# OutputPowerModule.net
KiCad netlist of a schematic drawn in Altium Designer
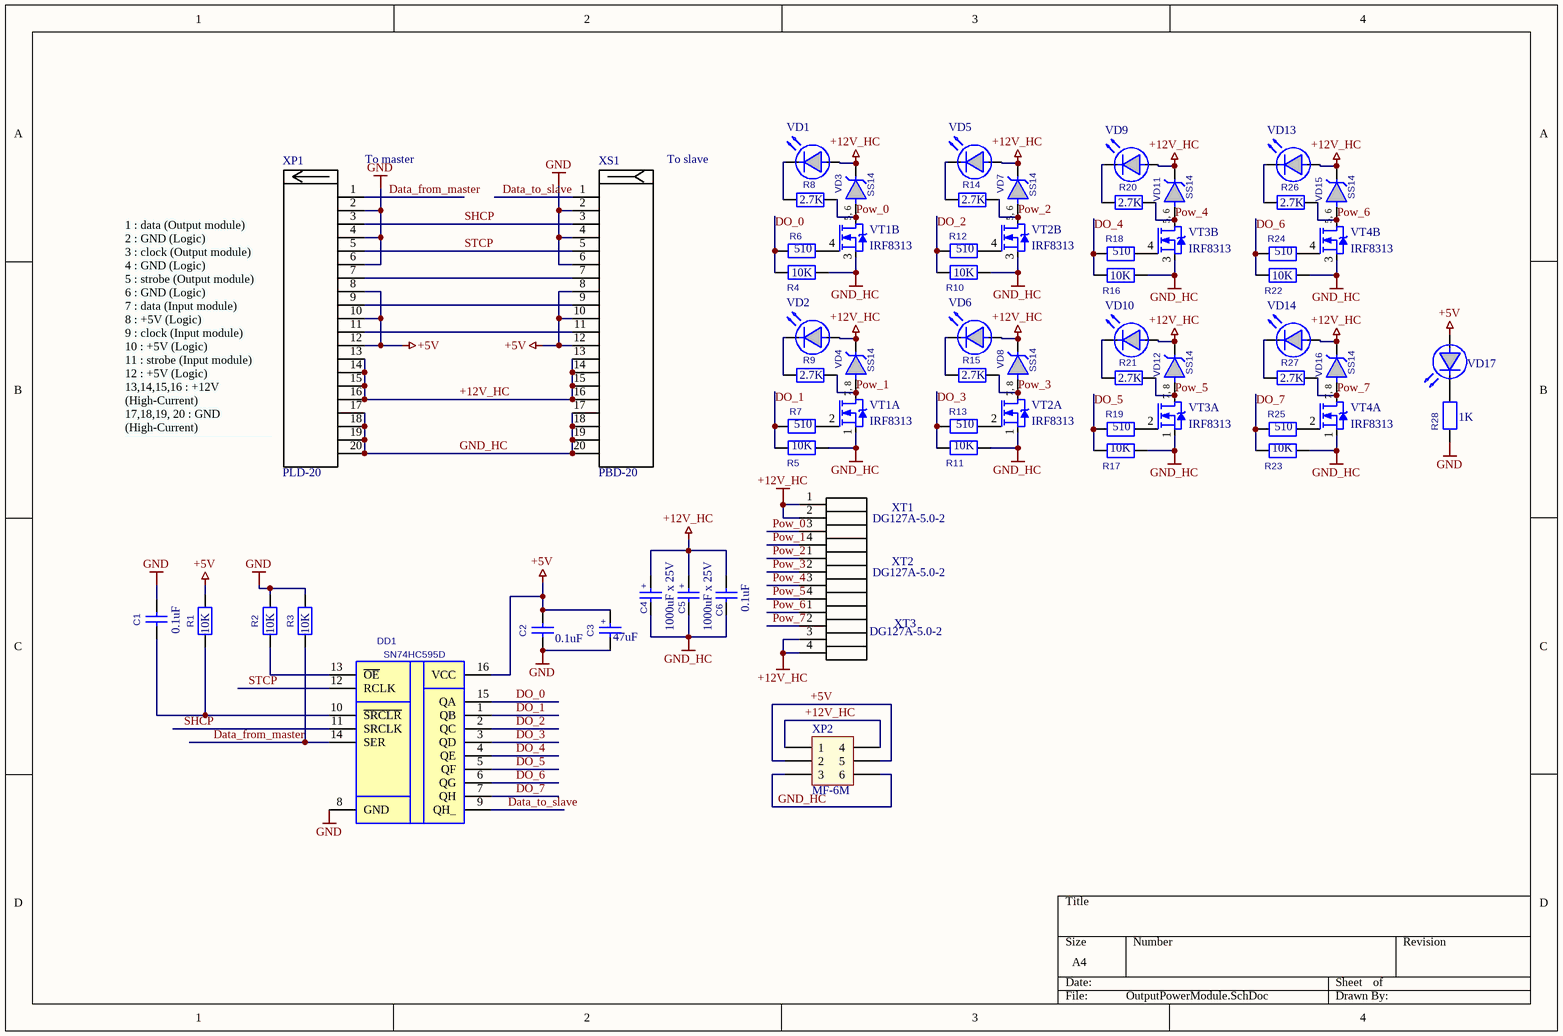
[diagram p0: OutputPowerModule.SchDoc]

(export (version "E")
  (design (tool "Eeschema 10.0.6"))
  (components
    (comp (ref "C1")
      (value "0.1uF")
      (footprint "C-1608[0603]")
      (description "C-0603")
      (libsource (lib "Altium-RC") (part "C-0603"))
    )
    (comp (ref "C2")
      (value "0.1uF")
      (footprint "C-1608[0603]")
      (description "C-0603")
      (libsource (lib "Altium-RC") (part "C-0603"))
    )
    (comp (ref "C3")
      (value "47uF")
      (footprint "C-CASE")
      (description "C-CCASE")
      (libsource (lib "Altium-RC") (part "C-CCASE"))
    )
    (comp (ref "C4")
      (value "1000uF x 25V")
      (footprint "D10-5MM")
      (description "K50-35(D10MM)")
      (libsource (lib "Altium-RC") (part "K50-35(D10MM)"))
    )
    (comp (ref "C5")
      (value "1000uF x 25V")
      (footprint "D10-5MM")
      (description "K50-35(D10MM)")
      (libsource (lib "Altium-RC") (part "K50-35(D10MM)"))
    )
    (comp (ref "C6")
      (value "0.1uF")
      (footprint "C-1608[0603]")
      (description "C-0603")
      (libsource (lib "Altium-RC") (part "C-0603"))
    )
    (comp (ref "DD1")
      (value "SN74HC595D")
      (footprint "SO-G16")
      (libsource (lib "Altium-IC") (part "SN74HC595D"))
    )
    (comp (ref "R1")
      (value "10K")
      (footprint "R-1608[0603]")
      (description "R-0603")
      (libsource (lib "Altium-RC") (part "R-0603"))
    )
    (comp (ref "R2")
      (value "10K")
      (footprint "R-1608[0603]")
      (description "R-0603")
      (libsource (lib "Altium-RC") (part "R-0603"))
    )
    (comp (ref "R3")
      (value "10K")
      (footprint "R-1608[0603]")
      (description "R-0603")
      (libsource (lib "Altium-RC") (part "R-0603"))
    )
    (comp (ref "R4")
      (value "10K")
      (footprint "R-1608[0603]")
      (description "R-0603")
      (libsource (lib "Altium-RC") (part "R-0603"))
    )
    (comp (ref "R5")
      (value "10K")
      (footprint "R-1608[0603]")
      (description "R-0603")
      (libsource (lib "Altium-RC") (part "R-0603"))
    )
    (comp (ref "R6")
      (value "510")
      (footprint "R-1608[0603]")
      (description "R-0603")
      (libsource (lib "Altium-RC") (part "R-0603"))
    )
    (comp (ref "R7")
      (value "510")
      (footprint "R-1608[0603]")
      (description "R-0603")
      (libsource (lib "Altium-RC") (part "R-0603"))
    )
    (comp (ref "R8")
      (value "2.7K")
      (footprint "R-1608[0603]")
      (description "R-0603")
      (libsource (lib "Altium-RC") (part "R-0603"))
    )
    (comp (ref "R9")
      (value "2.7K")
      (footprint "R-1608[0603]")
      (description "R-0603")
      (libsource (lib "Altium-RC") (part "R-0603"))
    )
    (comp (ref "R10")
      (value "10K")
      (footprint "R-1608[0603]")
      (description "R-0603")
      (libsource (lib "Altium-RC") (part "R-0603"))
    )
    (comp (ref "R11")
      (value "10K")
      (footprint "R-1608[0603]")
      (description "R-0603")
      (libsource (lib "Altium-RC") (part "R-0603"))
    )
    (comp (ref "R12")
      (value "510")
      (footprint "R-1608[0603]")
      (description "R-0603")
      (libsource (lib "Altium-RC") (part "R-0603"))
    )
    (comp (ref "R13")
      (value "510")
      (footprint "R-1608[0603]")
      (description "R-0603")
      (libsource (lib "Altium-RC") (part "R-0603"))
    )
    (comp (ref "R14")
      (value "2.7K")
      (footprint "R-1608[0603]")
      (description "R-0603")
      (libsource (lib "Altium-RC") (part "R-0603"))
    )
    (comp (ref "R15")
      (value "2.7K")
      (footprint "R-1608[0603]")
      (description "R-0603")
      (libsource (lib "Altium-RC") (part "R-0603"))
    )
    (comp (ref "R16")
      (value "10K")
      (footprint "R-1608[0603]")
      (description "R-0603")
      (libsource (lib "Altium-RC") (part "R-0603"))
    )
    (comp (ref "R17")
      (value "10K")
      (footprint "R-1608[0603]")
      (description "R-0603")
      (libsource (lib "Altium-RC") (part "R-0603"))
    )
    (comp (ref "R18")
      (value "510")
      (footprint "R-1608[0603]")
      (description "R-0603")
      (libsource (lib "Altium-RC") (part "R-0603"))
    )
    (comp (ref "R19")
      (value "510")
      (footprint "R-1608[0603]")
      (description "R-0603")
      (libsource (lib "Altium-RC") (part "R-0603"))
    )
    (comp (ref "R20")
      (value "2.7K")
      (footprint "R-1608[0603]")
      (description "R-0603")
      (libsource (lib "Altium-RC") (part "R-0603"))
    )
    (comp (ref "R21")
      (value "2.7K")
      (footprint "R-1608[0603]")
      (description "R-0603")
      (libsource (lib "Altium-RC") (part "R-0603"))
    )
    (comp (ref "R22")
      (value "10K")
      (footprint "R-1608[0603]")
      (description "R-0603")
      (libsource (lib "Altium-RC") (part "R-0603"))
    )
    (comp (ref "R23")
      (value "10K")
      (footprint "R-1608[0603]")
      (description "R-0603")
      (libsource (lib "Altium-RC") (part "R-0603"))
    )
    (comp (ref "R24")
      (value "510")
      (footprint "R-1608[0603]")
      (description "R-0603")
      (libsource (lib "Altium-RC") (part "R-0603"))
    )
    (comp (ref "R25")
      (value "510")
      (footprint "R-1608[0603]")
      (description "R-0603")
      (libsource (lib "Altium-RC") (part "R-0603"))
    )
    (comp (ref "R26")
      (value "2.7K")
      (footprint "R-1608[0603]")
      (description "R-0603")
      (libsource (lib "Altium-RC") (part "R-0603"))
    )
    (comp (ref "R27")
      (value "2.7K")
      (footprint "R-1608[0603]")
      (description "R-0603")
      (libsource (lib "Altium-RC") (part "R-0603"))
    )
    (comp (ref "R28")
      (value "1K")
      (footprint "R-1608[0603]")
      (description "R-0603")
      (libsource (lib "Altium-RC") (part "R-0603"))
    )
    (comp (ref "VD1")
      (value "L-C191KGCT")
      (footprint "LED-0603")
      (description "0603 Green Led")
      (libsource (lib "Altium-OPTO") (part "L-C191KGCT"))
    )
    (comp (ref "VD2")
      (value "L-C191KGCT")
      (footprint "LED-0603")
      (description "0603 Green Led")
      (libsource (lib "Altium-OPTO") (part "L-C191KGCT"))
    )
    (comp (ref "VD3") (value "SS14") (footprint "SMA") (libsource (lib "Altium-RECT") (part "SS16")))
    (comp (ref "VD4") (value "SS14") (footprint "SMA") (libsource (lib "Altium-RECT") (part "SS16")))
    (comp (ref "VD5")
      (value "L-C191KGCT")
      (footprint "LED-0603")
      (description "0603 Green Led")
      (libsource (lib "Altium-OPTO") (part "L-C191KGCT"))
    )
    (comp (ref "VD6")
      (value "L-C191KGCT")
      (footprint "LED-0603")
      (description "0603 Green Led")
      (libsource (lib "Altium-OPTO") (part "L-C191KGCT"))
    )
    (comp (ref "VD7") (value "SS14") (footprint "SMA") (libsource (lib "Altium-RECT") (part "SS16")))
    (comp (ref "VD8") (value "SS14") (footprint "SMA") (libsource (lib "Altium-RECT") (part "SS16")))
    (comp (ref "VD9")
      (value "L-C191KGCT")
      (footprint "LED-0603")
      (description "0603 Green Led")
      (libsource (lib "Altium-OPTO") (part "L-C191KGCT"))
    )
    (comp (ref "VD10")
      (value "L-C191KGCT")
      (footprint "LED-0603")
      (description "0603 Green Led")
      (libsource (lib "Altium-OPTO") (part "L-C191KGCT"))
    )
    (comp (ref "VD11") (value "SS14") (footprint "SMA") (libsource (lib "Altium-RECT") (part "SS16")))
    (comp (ref "VD12") (value "SS14") (footprint "SMA") (libsource (lib "Altium-RECT") (part "SS16")))
    (comp (ref "VD13")
      (value "L-C191KGCT")
      (footprint "LED-0603")
      (description "0603 Green Led")
      (libsource (lib "Altium-OPTO") (part "L-C191KGCT"))
    )
    (comp (ref "VD14")
      (value "L-C191KGCT")
      (footprint "LED-0603")
      (description "0603 Green Led")
      (libsource (lib "Altium-OPTO") (part "L-C191KGCT"))
    )
    (comp (ref "VD15") (value "SS14") (footprint "SMA") (libsource (lib "Altium-RECT") (part "SS16")))
    (comp (ref "VD16") (value "SS14") (footprint "SMA") (libsource (lib "Altium-RECT") (part "SS16")))
    (comp (ref "VD17")
      (value "L-C191KGCT")
      (footprint "LED-0603")
      (description "0603 Green Led")
      (libsource (lib "") (part "L-C191KGCT_1"))
    )
    (comp (ref "VT1")
      (value "IRF8313")
      (footprint "SO8")
      (description "HEXFET Power MOSFET N channel")
      (libsource (lib "Altium-RECT") (part "IRF8313"))
    )
    (comp (ref "VT2")
      (value "IRF8313")
      (footprint "SO8")
      (description "HEXFET Power MOSFET N channel")
      (libsource (lib "Altium-RECT") (part "IRF8313"))
    )
    (comp (ref "VT3")
      (value "IRF8313")
      (footprint "SO8")
      (description "HEXFET Power MOSFET N channel")
      (libsource (lib "Altium-RECT") (part "IRF8313"))
    )
    (comp (ref "VT4")
      (value "IRF8313")
      (footprint "SO8")
      (description "HEXFET Power MOSFET N channel")
      (libsource (lib "Altium-RECT") (part "IRF8313"))
    )
    (comp (ref "XP1")
      (value "PLD-20")
      (footprint "PLD-20 ROT")
      (description "20 pin, 2 row, MALE connector")
      (libsource (lib "Altium-CONN") (part "PLD-20"))
    )
    (comp (ref "XP2")
      (value "MF-6M")
      (footprint "MF-6M")
      (description "Molex Male connector")
      (libsource (lib "Altium-CONN") (part "MF-6M"))
    )
    (comp (ref "XS1")
      (value "PBD-20")
      (footprint "PBD-20 Rot")
      (description "2.54mm, 20 pin FEMALE connector")
      (libsource (lib "Altium-CONN") (part "PBD-20"))
    )
    (comp (ref "XT1")
      (value "DG127A-5.0-2")
      (footprint "DG127A-5.0-2")
      (description "Клеммник винтовой двухр дный шаг 5.0 мм 2х2 контактов")
      (libsource (lib "Altium-CONN") (part "DG127A-5.0-2"))
    )
    (comp (ref "XT2")
      (value "DG127A-5.0-2")
      (footprint "DG127A-5.0-2")
      (description "Клеммник винтовой двухр дный шаг 5.0 мм 2х2 контактов")
      (libsource (lib "Altium-CONN") (part "DG127A-5.0-2"))
    )
    (comp (ref "XT3")
      (value "DG127A-5.0-2")
      (footprint "DG127A-5.0-2")
      (description "Клеммник винтовой двухр дный шаг 5.0 мм 2х2 контактов")
      (libsource (lib "Altium-CONN") (part "DG127A-5.0-2"))
    )
  )
  (nets
    (net (code "1") (name "+5V") (class "Default")
      (node (ref "C2") (pin "1") (pintype "passive"))
      (node (ref "C3") (pin "1") (pinfunction "+_1") (pintype "passive"))
      (node (ref "DD1") (pin "16") (pinfunction "VCC_16") (pintype "passive"))
      (node (ref "R1") (pin "2") (pinfunction "2_2") (pintype "passive"))
      (node (ref "VD17") (pin "2") (pinfunction "A_2") (pintype "passive"))
      (node (ref "XP1") (pin "10") (pintype "passive"))
      (node (ref "XP1") (pin "12") (pintype "passive"))
      (node (ref "XP1") (pin "8") (pintype "passive"))
      (node (ref "XP2") (pin "2") (pinfunction "2_2") (pintype "passive"))
      (node (ref "XP2") (pin "5") (pinfunction "5_5") (pintype "passive"))
      (node (ref "XS1") (pin "10") (pintype "passive"))
      (node (ref "XS1") (pin "12") (pintype "passive"))
      (node (ref "XS1") (pin "8") (pintype "passive"))
    )
    (net (code "2") (name "+12V_HC") (class "Default")
      (node (ref "C4") (pin "1") (pinfunction "+_1") (pintype "passive"))
      (node (ref "C5") (pin "1") (pinfunction "+_1") (pintype "passive"))
      (node (ref "C6") (pin "1") (pintype "passive"))
      (node (ref "VD1") (pin "2") (pinfunction "A_2") (pintype "passive"))
      (node (ref "VD10") (pin "2") (pinfunction "A_2") (pintype "passive"))
      (node (ref "VD11") (pin "1") (pinfunction "K_1") (pintype "passive"))
      (node (ref "VD12") (pin "1") (pinfunction "K_1") (pintype "passive"))
      (node (ref "VD13") (pin "2") (pinfunction "A_2") (pintype "passive"))
      (node (ref "VD14") (pin "2") (pinfunction "A_2") (pintype "passive"))
      (node (ref "VD15") (pin "1") (pinfunction "K_1") (pintype "passive"))
      (node (ref "VD16") (pin "1") (pinfunction "K_1") (pintype "passive"))
      (node (ref "VD2") (pin "2") (pinfunction "A_2") (pintype "passive"))
      (node (ref "VD3") (pin "1") (pinfunction "K_1") (pintype "passive"))
      (node (ref "VD4") (pin "1") (pinfunction "K_1") (pintype "passive"))
      (node (ref "VD5") (pin "2") (pinfunction "A_2") (pintype "passive"))
      (node (ref "VD6") (pin "2") (pinfunction "A_2") (pintype "passive"))
      (node (ref "VD7") (pin "1") (pinfunction "K_1") (pintype "passive"))
      (node (ref "VD8") (pin "1") (pinfunction "K_1") (pintype "passive"))
      (node (ref "VD9") (pin "2") (pinfunction "A_2") (pintype "passive"))
      (node (ref "XP1") (pin "13") (pintype "passive"))
      (node (ref "XP1") (pin "14") (pintype "passive"))
      (node (ref "XP1") (pin "15") (pintype "passive"))
      (node (ref "XP1") (pin "16") (pintype "passive"))
      (node (ref "XP2") (pin "1") (pinfunction "1_1") (pintype "passive"))
      (node (ref "XP2") (pin "4") (pinfunction "4_4") (pintype "passive"))
      (node (ref "XS1") (pin "13") (pintype "passive"))
      (node (ref "XS1") (pin "14") (pintype "passive"))
      (node (ref "XS1") (pin "15") (pintype "passive"))
      (node (ref "XS1") (pin "16") (pintype "passive"))
      (node (ref "XT1") (pin "1") (pinfunction "1_1") (pintype "passive"))
      (node (ref "XT1") (pin "2") (pinfunction "2_2") (pintype "passive"))
      (node (ref "XT3") (pin "3") (pinfunction "3_3") (pintype "passive"))
      (node (ref "XT3") (pin "4") (pinfunction "4_4") (pintype "passive"))
    )
    (net (code "3") (name "/DO_0") (class "Default")
      (node (ref "DD1") (pin "15") (pinfunction "QA_15") (pintype "passive"))
      (node (ref "R4") (pin "1") (pinfunction "1_1") (pintype "passive"))
      (node (ref "R6") (pin "2") (pinfunction "2_2") (pintype "passive"))
    )
    (net (code "4") (name "/DO_1") (class "Default")
      (node (ref "DD1") (pin "1") (pinfunction "QB_1") (pintype "passive"))
      (node (ref "R5") (pin "1") (pinfunction "1_1") (pintype "passive"))
      (node (ref "R7") (pin "2") (pinfunction "2_2") (pintype "passive"))
    )
    (net (code "5") (name "/DO_2") (class "Default")
      (node (ref "DD1") (pin "2") (pinfunction "QC_2") (pintype "passive"))
      (node (ref "R10") (pin "1") (pinfunction "1_1") (pintype "passive"))
      (node (ref "R12") (pin "2") (pinfunction "2_2") (pintype "passive"))
    )
    (net (code "6") (name "/DO_3") (class "Default")
      (node (ref "DD1") (pin "3") (pinfunction "QD_3") (pintype "passive"))
      (node (ref "R11") (pin "1") (pinfunction "1_1") (pintype "passive"))
      (node (ref "R13") (pin "2") (pinfunction "2_2") (pintype "passive"))
    )
    (net (code "7") (name "/DO_4") (class "Default")
      (node (ref "DD1") (pin "4") (pinfunction "QE_4") (pintype "passive"))
      (node (ref "R16") (pin "1") (pinfunction "1_1") (pintype "passive"))
      (node (ref "R18") (pin "2") (pinfunction "2_2") (pintype "passive"))
    )
    (net (code "8") (name "/DO_5") (class "Default")
      (node (ref "DD1") (pin "5") (pinfunction "QF_5") (pintype "passive"))
      (node (ref "R17") (pin "1") (pinfunction "1_1") (pintype "passive"))
      (node (ref "R19") (pin "2") (pinfunction "2_2") (pintype "passive"))
    )
    (net (code "9") (name "/DO_6") (class "Default")
      (node (ref "DD1") (pin "6") (pinfunction "QG_6") (pintype "passive"))
      (node (ref "R22") (pin "1") (pinfunction "1_1") (pintype "passive"))
      (node (ref "R24") (pin "2") (pinfunction "2_2") (pintype "passive"))
    )
    (net (code "10") (name "/DO_7") (class "Default")
      (node (ref "DD1") (pin "7") (pinfunction "QH_7") (pintype "passive"))
      (node (ref "R23") (pin "1") (pinfunction "1_1") (pintype "passive"))
      (node (ref "R25") (pin "2") (pinfunction "2_2") (pintype "passive"))
    )
    (net (code "11") (name "/Data_from_master") (class "Default")
      (node (ref "DD1") (pin "14") (pinfunction "SER_14") (pintype "passive"))
      (node (ref "R3") (pin "1") (pinfunction "1_1") (pintype "passive"))
      (node (ref "XP1") (pin "1") (pintype "passive"))
    )
    (net (code "12") (name "/Data_to_slave") (class "Default")
      (node (ref "DD1") (pin "9") (pinfunction "QH__9") (pintype "passive"))
      (node (ref "XS1") (pin "1") (pintype "passive"))
    )
    (net (code "13") (name "/Pow_0") (class "Default")
      (node (ref "R8") (pin "2") (pinfunction "2_2") (pintype "passive"))
      (node (ref "VD3") (pin "2") (pinfunction "A_2") (pintype "passive"))
      (node (ref "VT1") (pin "5") (pinfunction "D_5") (pintype "passive"))
      (node (ref "VT1") (pin "6") (pinfunction "D_6") (pintype "passive"))
      (node (ref "XT1") (pin "3") (pinfunction "3_3") (pintype "passive"))
    )
    (net (code "14") (name "/Pow_1") (class "Default")
      (node (ref "R9") (pin "2") (pinfunction "2_2") (pintype "passive"))
      (node (ref "VD4") (pin "2") (pinfunction "A_2") (pintype "passive"))
      (node (ref "VT1") (pin "7") (pinfunction "D_7") (pintype "passive"))
      (node (ref "VT1") (pin "8") (pinfunction "D_8") (pintype "passive"))
      (node (ref "XT1") (pin "4") (pinfunction "4_4") (pintype "passive"))
    )
    (net (code "15") (name "/Pow_2") (class "Default")
      (node (ref "R14") (pin "2") (pinfunction "2_2") (pintype "passive"))
      (node (ref "VD7") (pin "2") (pinfunction "A_2") (pintype "passive"))
      (node (ref "VT2") (pin "5") (pinfunction "D_5") (pintype "passive"))
      (node (ref "VT2") (pin "6") (pinfunction "D_6") (pintype "passive"))
      (node (ref "XT2") (pin "1") (pinfunction "1_1") (pintype "passive"))
    )
    (net (code "16") (name "/Pow_3") (class "Default")
      (node (ref "R15") (pin "2") (pinfunction "2_2") (pintype "passive"))
      (node (ref "VD8") (pin "2") (pinfunction "A_2") (pintype "passive"))
      (node (ref "VT2") (pin "7") (pinfunction "D_7") (pintype "passive"))
      (node (ref "VT2") (pin "8") (pinfunction "D_8") (pintype "passive"))
      (node (ref "XT2") (pin "2") (pinfunction "2_2") (pintype "passive"))
    )
    (net (code "17") (name "/Pow_4") (class "Default")
      (node (ref "R20") (pin "2") (pinfunction "2_2") (pintype "passive"))
      (node (ref "VD11") (pin "2") (pinfunction "A_2") (pintype "passive"))
      (node (ref "VT3") (pin "5") (pinfunction "D_5") (pintype "passive"))
      (node (ref "VT3") (pin "6") (pinfunction "D_6") (pintype "passive"))
      (node (ref "XT2") (pin "3") (pinfunction "3_3") (pintype "passive"))
    )
    (net (code "18") (name "/Pow_5") (class "Default")
      (node (ref "R21") (pin "2") (pinfunction "2_2") (pintype "passive"))
      (node (ref "VD12") (pin "2") (pinfunction "A_2") (pintype "passive"))
      (node (ref "VT3") (pin "7") (pinfunction "D_7") (pintype "passive"))
      (node (ref "VT3") (pin "8") (pinfunction "D_8") (pintype "passive"))
      (node (ref "XT2") (pin "4") (pinfunction "4_4") (pintype "passive"))
    )
    (net (code "19") (name "/Pow_6") (class "Default")
      (node (ref "R26") (pin "2") (pinfunction "2_2") (pintype "passive"))
      (node (ref "VD15") (pin "2") (pinfunction "A_2") (pintype "passive"))
      (node (ref "VT4") (pin "5") (pinfunction "D_5") (pintype "passive"))
      (node (ref "VT4") (pin "6") (pinfunction "D_6") (pintype "passive"))
      (node (ref "XT3") (pin "1") (pinfunction "1_1") (pintype "passive"))
    )
    (net (code "20") (name "/Pow_7") (class "Default")
      (node (ref "R27") (pin "2") (pinfunction "2_2") (pintype "passive"))
      (node (ref "VD16") (pin "2") (pinfunction "A_2") (pintype "passive"))
      (node (ref "VT4") (pin "7") (pinfunction "D_7") (pintype "passive"))
      (node (ref "VT4") (pin "8") (pinfunction "D_8") (pintype "passive"))
      (node (ref "XT3") (pin "2") (pinfunction "2_2") (pintype "passive"))
    )
    (net (code "21") (name "/SHCP") (class "Default")
      (node (ref "DD1") (pin "11") (pinfunction "SRCLK_11") (pintype "passive"))
      (node (ref "XP1") (pin "3") (pintype "passive"))
      (node (ref "XS1") (pin "3") (pintype "passive"))
    )
    (net (code "22") (name "/STCP") (class "Default")
      (node (ref "DD1") (pin "12") (pinfunction "RCLK_12") (pintype "passive"))
      (node (ref "XP1") (pin "5") (pintype "passive"))
      (node (ref "XS1") (pin "5") (pintype "passive"))
    )
    (net (code "23") (name "GND") (class "Default")
      (node (ref "C1") (pin "1") (pintype "passive"))
      (node (ref "C2") (pin "2") (pintype "passive"))
      (node (ref "C3") (pin "2") (pinfunction "-_2") (pintype "passive"))
      (node (ref "DD1") (pin "8") (pinfunction "GND_8") (pintype "passive"))
      (node (ref "R2") (pin "2") (pinfunction "2_2") (pintype "passive"))
      (node (ref "R28") (pin "2") (pinfunction "2_2") (pintype "passive"))
      (node (ref "R3") (pin "2") (pinfunction "2_2") (pintype "passive"))
      (node (ref "XP1") (pin "2") (pintype "passive"))
      (node (ref "XP1") (pin "4") (pintype "passive"))
      (node (ref "XP1") (pin "6") (pintype "passive"))
      (node (ref "XS1") (pin "2") (pintype "passive"))
      (node (ref "XS1") (pin "4") (pintype "passive"))
      (node (ref "XS1") (pin "6") (pintype "passive"))
    )
    (net (code "24") (name "GND_HC") (class "Default")
      (node (ref "C4") (pin "2") (pinfunction "-_2") (pintype "passive"))
      (node (ref "C5") (pin "2") (pinfunction "-_2") (pintype "passive"))
      (node (ref "C6") (pin "2") (pintype "passive"))
      (node (ref "R10") (pin "2") (pinfunction "2_2") (pintype "passive"))
      (node (ref "R11") (pin "2") (pinfunction "2_2") (pintype "passive"))
      (node (ref "R16") (pin "2") (pinfunction "2_2") (pintype "passive"))
      (node (ref "R17") (pin "2") (pinfunction "2_2") (pintype "passive"))
      (node (ref "R22") (pin "2") (pinfunction "2_2") (pintype "passive"))
      (node (ref "R23") (pin "2") (pinfunction "2_2") (pintype "passive"))
      (node (ref "R4") (pin "2") (pinfunction "2_2") (pintype "passive"))
      (node (ref "R5") (pin "2") (pinfunction "2_2") (pintype "passive"))
      (node (ref "VT1") (pin "1") (pinfunction "S_1") (pintype "passive"))
      (node (ref "VT1") (pin "3") (pinfunction "S_3") (pintype "passive"))
      (node (ref "VT2") (pin "1") (pinfunction "S_1") (pintype "passive"))
      (node (ref "VT2") (pin "3") (pinfunction "S_3") (pintype "passive"))
      (node (ref "VT3") (pin "1") (pinfunction "S_1") (pintype "passive"))
      (node (ref "VT3") (pin "3") (pinfunction "S_3") (pintype "passive"))
      (node (ref "VT4") (pin "1") (pinfunction "S_1") (pintype "passive"))
      (node (ref "VT4") (pin "3") (pinfunction "S_3") (pintype "passive"))
      (node (ref "XP1") (pin "17") (pintype "passive"))
      (node (ref "XP1") (pin "18") (pintype "passive"))
      (node (ref "XP1") (pin "19") (pintype "passive"))
      (node (ref "XP1") (pin "20") (pintype "passive"))
      (node (ref "XP2") (pin "3") (pinfunction "3_3") (pintype "passive"))
      (node (ref "XP2") (pin "6") (pinfunction "6_6") (pintype "passive"))
      (node (ref "XS1") (pin "17") (pintype "passive"))
      (node (ref "XS1") (pin "18") (pintype "passive"))
      (node (ref "XS1") (pin "19") (pintype "passive"))
      (node (ref "XS1") (pin "20") (pintype "passive"))
    )
    (net (code "25") (name "Net-(DD1-~{OE})") (class "Default")
      (node (ref "DD1") (pin "13") (pinfunction "~{OE}_13") (pintype "passive"))
      (node (ref "R2") (pin "1") (pinfunction "1_1") (pintype "passive"))
    )
    (net (code "26") (name "Net-(DD1-~{SRCLR})") (class "Default")
      (node (ref "C1") (pin "2") (pintype "passive"))
      (node (ref "DD1") (pin "10") (pinfunction "~{SRCLR}_10") (pintype "passive"))
      (node (ref "R1") (pin "1") (pinfunction "1_1") (pintype "passive"))
    )
    (net (code "27") (name "Net-(VD1-K)") (class "Default")
      (node (ref "R8") (pin "1") (pinfunction "1_1") (pintype "passive"))
      (node (ref "VD1") (pin "1") (pinfunction "K_1") (pintype "passive"))
    )
    (net (code "28") (name "Net-(VD2-K)") (class "Default")
      (node (ref "R9") (pin "1") (pinfunction "1_1") (pintype "passive"))
      (node (ref "VD2") (pin "1") (pinfunction "K_1") (pintype "passive"))
    )
    (net (code "29") (name "Net-(VD5-K)") (class "Default")
      (node (ref "R14") (pin "1") (pinfunction "1_1") (pintype "passive"))
      (node (ref "VD5") (pin "1") (pinfunction "K_1") (pintype "passive"))
    )
    (net (code "30") (name "Net-(VD6-K)") (class "Default")
      (node (ref "R15") (pin "1") (pinfunction "1_1") (pintype "passive"))
      (node (ref "VD6") (pin "1") (pinfunction "K_1") (pintype "passive"))
    )
    (net (code "31") (name "Net-(VD9-K)") (class "Default")
      (node (ref "R20") (pin "1") (pinfunction "1_1") (pintype "passive"))
      (node (ref "VD9") (pin "1") (pinfunction "K_1") (pintype "passive"))
    )
    (net (code "32") (name "Net-(VD10-K)") (class "Default")
      (node (ref "R21") (pin "1") (pinfunction "1_1") (pintype "passive"))
      (node (ref "VD10") (pin "1") (pinfunction "K_1") (pintype "passive"))
    )
    (net (code "33") (name "Net-(VD13-K)") (class "Default")
      (node (ref "R26") (pin "1") (pinfunction "1_1") (pintype "passive"))
      (node (ref "VD13") (pin "1") (pinfunction "K_1") (pintype "passive"))
    )
    (net (code "34") (name "Net-(VD14-K)") (class "Default")
      (node (ref "R27") (pin "1") (pinfunction "1_1") (pintype "passive"))
      (node (ref "VD14") (pin "1") (pinfunction "K_1") (pintype "passive"))
    )
    (net (code "35") (name "Net-(VD17-K)") (class "Default")
      (node (ref "R28") (pin "1") (pinfunction "1_1") (pintype "passive"))
      (node (ref "VD17") (pin "1") (pinfunction "K_1") (pintype "passive"))
    )
    (net (code "36") (name "Net-(VT1A-G)") (class "Default")
      (node (ref "R7") (pin "1") (pinfunction "1_1") (pintype "passive"))
      (node (ref "VT1") (pin "2") (pinfunction "G_2") (pintype "passive"))
    )
    (net (code "37") (name "Net-(VT1B-G)") (class "Default")
      (node (ref "R6") (pin "1") (pinfunction "1_1") (pintype "passive"))
      (node (ref "VT1") (pin "4") (pinfunction "G_4") (pintype "passive"))
    )
    (net (code "38") (name "Net-(VT2A-G)") (class "Default")
      (node (ref "R13") (pin "1") (pinfunction "1_1") (pintype "passive"))
      (node (ref "VT2") (pin "2") (pinfunction "G_2") (pintype "passive"))
    )
    (net (code "39") (name "Net-(VT2B-G)") (class "Default")
      (node (ref "R12") (pin "1") (pinfunction "1_1") (pintype "passive"))
      (node (ref "VT2") (pin "4") (pinfunction "G_4") (pintype "passive"))
    )
    (net (code "40") (name "Net-(VT3A-G)") (class "Default")
      (node (ref "R19") (pin "1") (pinfunction "1_1") (pintype "passive"))
      (node (ref "VT3") (pin "2") (pinfunction "G_2") (pintype "passive"))
    )
    (net (code "41") (name "Net-(VT3B-G)") (class "Default")
      (node (ref "R18") (pin "1") (pinfunction "1_1") (pintype "passive"))
      (node (ref "VT3") (pin "4") (pinfunction "G_4") (pintype "passive"))
    )
    (net (code "42") (name "Net-(VT4A-G)") (class "Default")
      (node (ref "R25") (pin "1") (pinfunction "1_1") (pintype "passive"))
      (node (ref "VT4") (pin "2") (pinfunction "G_2") (pintype "passive"))
    )
    (net (code "43") (name "Net-(VT4B-G)") (class "Default")
      (node (ref "R24") (pin "1") (pinfunction "1_1") (pintype "passive"))
      (node (ref "VT4") (pin "4") (pinfunction "G_4") (pintype "passive"))
    )
    (net (code "44") (name "Net-(XP1-Pad7)") (class "Default")
      (node (ref "XP1") (pin "7") (pintype "passive"))
      (node (ref "XS1") (pin "7") (pintype "passive"))
    )
    (net (code "45") (name "Net-(XP1-Pad9)") (class "Default")
      (node (ref "XP1") (pin "9") (pintype "passive"))
      (node (ref "XS1") (pin "9") (pintype "passive"))
    )
    (net (code "46") (name "Net-(XP1-Pad11)") (class "Default")
      (node (ref "XP1") (pin "11") (pintype "passive"))
      (node (ref "XS1") (pin "11") (pintype "passive"))
    )
  )
)
